# SCH_tic-tac_2024-06-27.net
KiCad netlist of a schematic drawn in EasyEDA
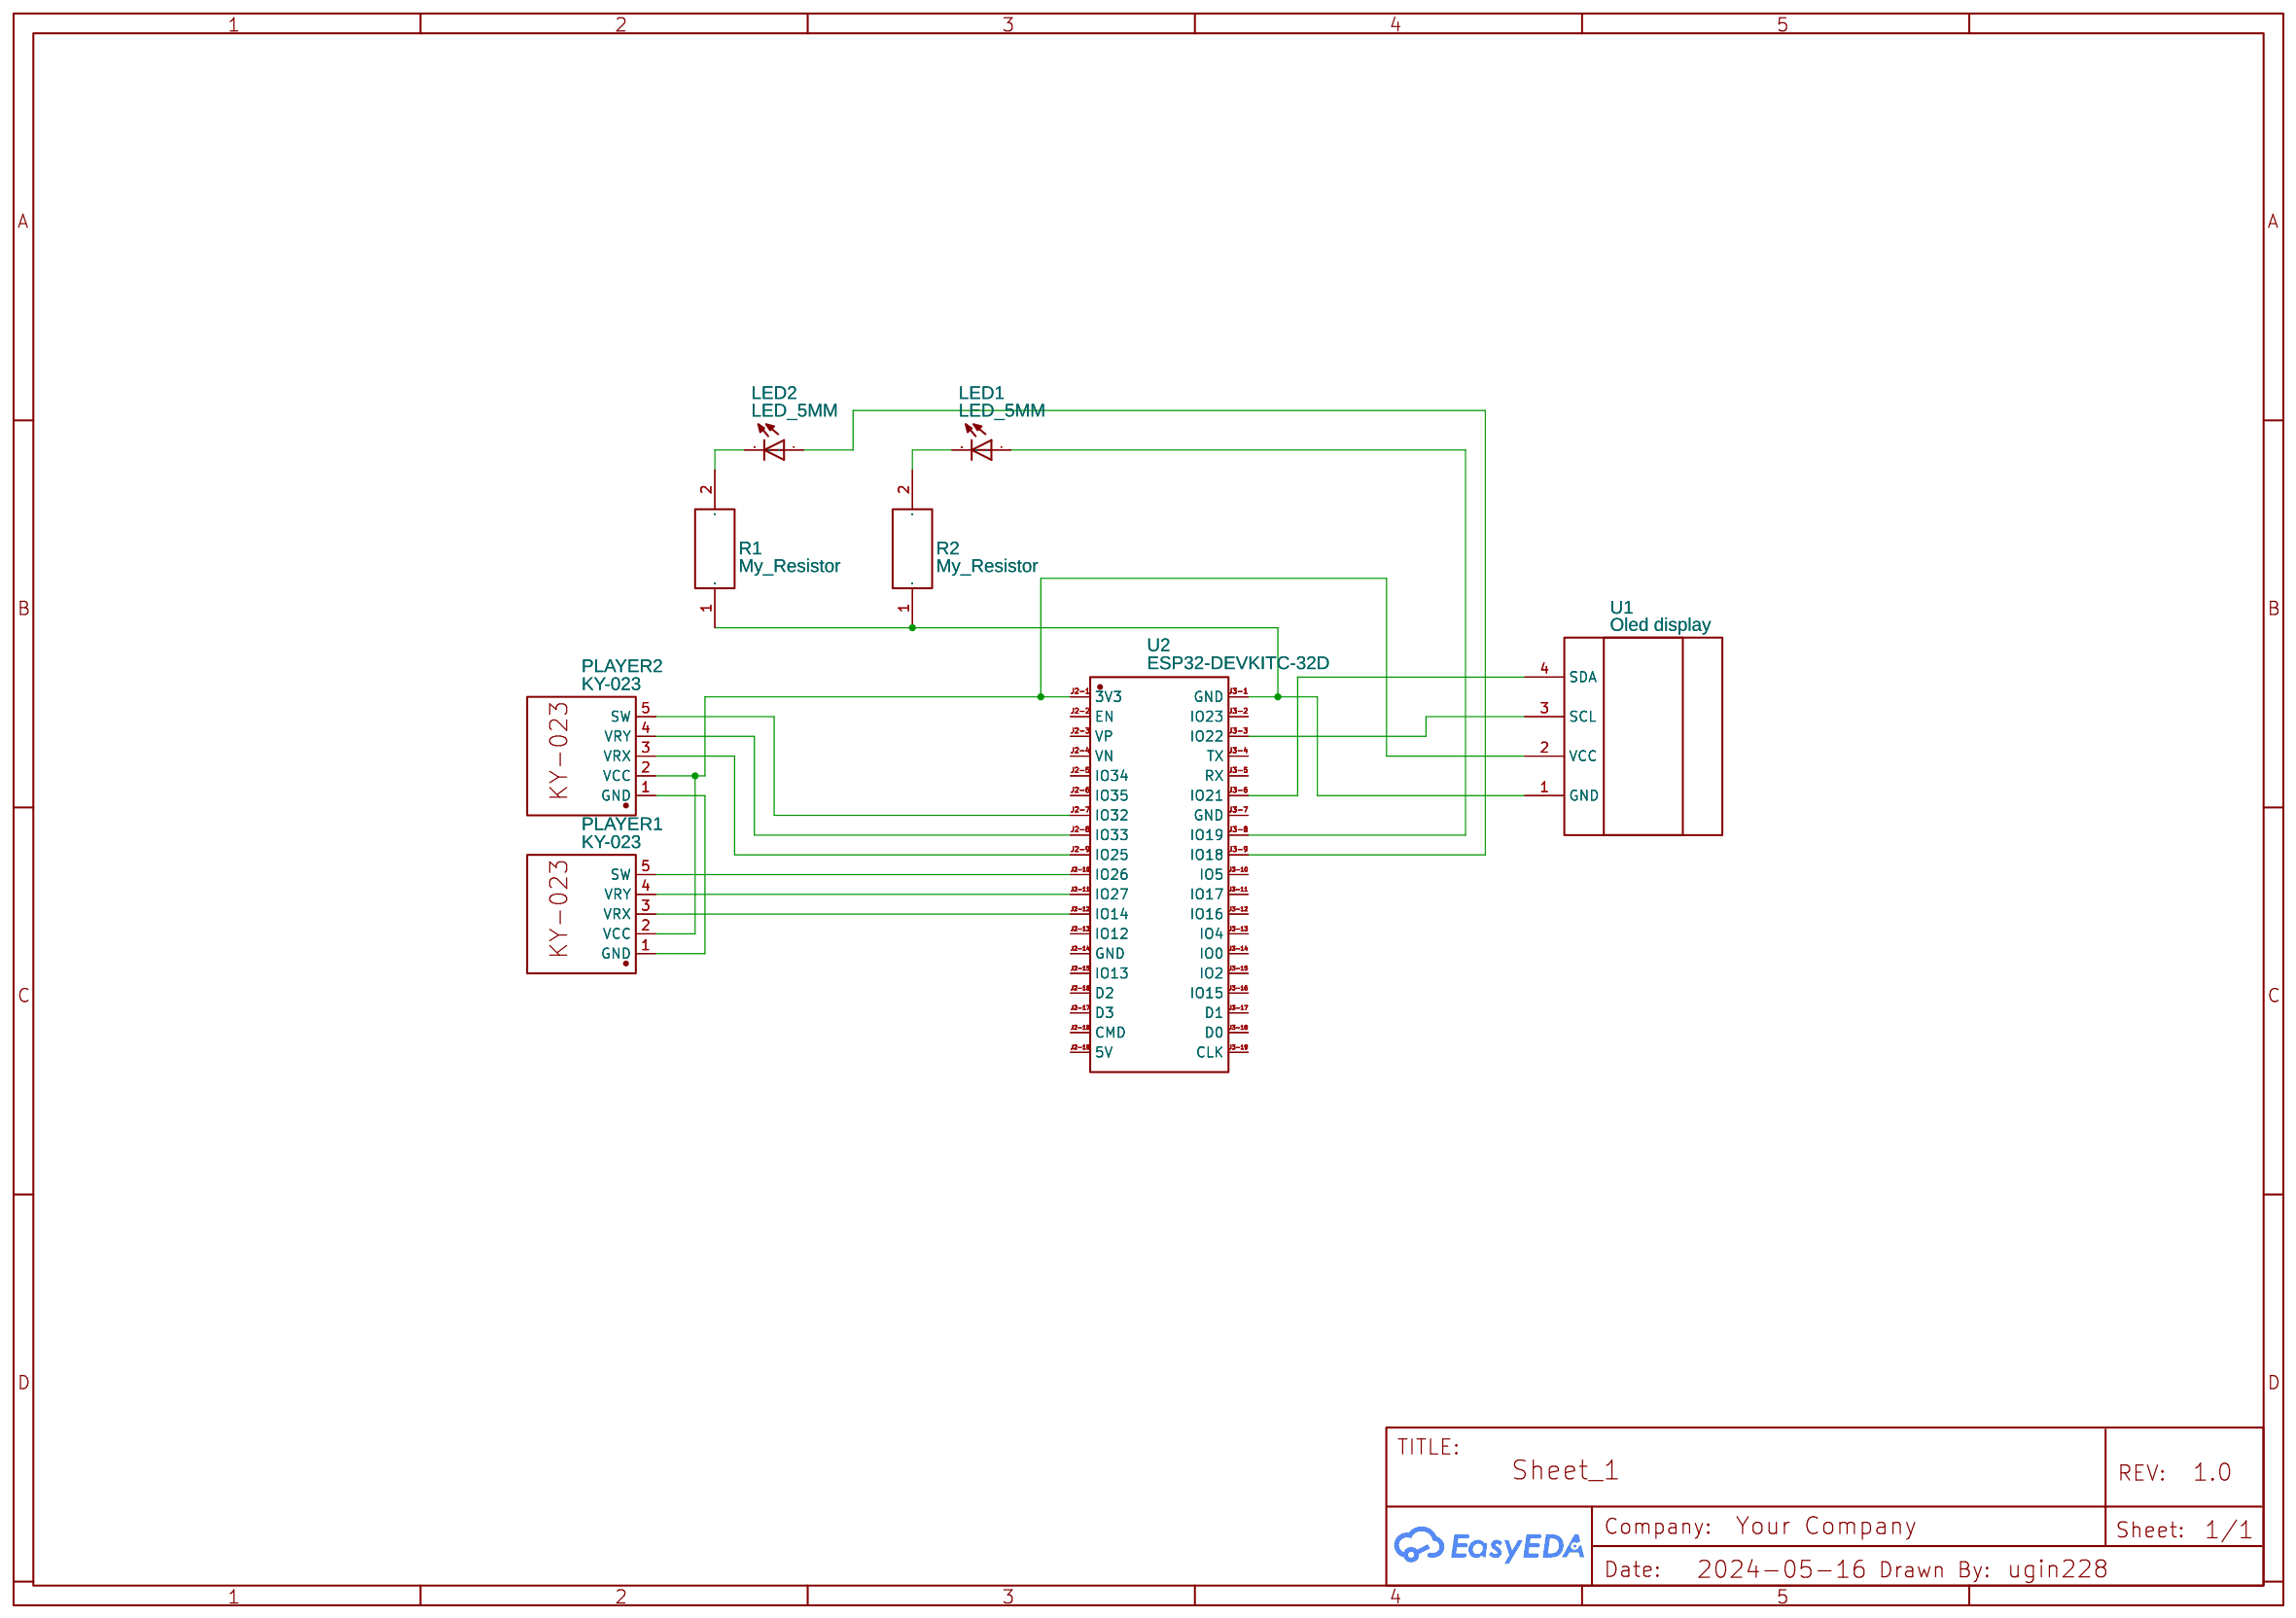
[diagram p0: schematic sheet]

(export (version "E")
  (design (tool "Eeschema 10.0.6"))
  (components
    (comp (ref "LED1") (value "LED_5MM") (libsource (lib "") (part "LED_5MM")))
    (comp (ref "LED2") (value "LED_5MM") (libsource (lib "") (part "LED_5MM")))
    (comp (ref "PLAYER1") (value "KY-023") (libsource (lib "") (part "KY-023")))
    (comp (ref "PLAYER2") (value "KY-023") (libsource (lib "") (part "KY-023")))
    (comp (ref "R1") (value "My_Resistor") (libsource (lib "") (part "My_Resistor")))
    (comp (ref "R2") (value "My_Resistor") (libsource (lib "") (part "My_Resistor")))
    (comp (ref "U1") (value "Oled display") (libsource (lib "") (part "Oled display")))
    (comp (ref "U2")
      (value "ESP32-DEVKITC-32D")
      (fields
        (field (name "Manufacturer Part") "ESP32-DevKitC-32D")
        (field (name "Manufacturer") "ESPRESSIF(乐鑫)")
      )
      (libsource (lib "") (part "ESP32-DEVKITC-32D"))
    )
  )
  (nets
    (net (code "1") (name "Net-(LED1-A)") (class "Default")
      (node (ref "LED1") (pin "1") (pinfunction "A_1") (pintype "unspecified"))
      (node (ref "U2") (pin "J3-8") (pinfunction "IO19_J3-8") (pintype "unspecified"))
    )
    (net (code "2") (name "Net-(LED1-C)") (class "Default")
      (node (ref "LED1") (pin "2") (pinfunction "C_2") (pintype "unspecified"))
      (node (ref "R2") (pin "2") (pinfunction "2_2") (pintype "unspecified"))
    )
    (net (code "3") (name "Net-(LED2-A)") (class "Default")
      (node (ref "LED2") (pin "1") (pinfunction "A_1") (pintype "unspecified"))
      (node (ref "U2") (pin "J3-9") (pinfunction "IO18_J3-9") (pintype "unspecified"))
    )
    (net (code "4") (name "Net-(LED2-C)") (class "Default")
      (node (ref "LED2") (pin "2") (pinfunction "C_2") (pintype "unspecified"))
      (node (ref "R1") (pin "2") (pinfunction "2_2") (pintype "unspecified"))
    )
    (net (code "5") (name "Net-(PLAYER1-GND)") (class "Default")
      (node (ref "PLAYER1") (pin "1") (pinfunction "GND_1") (pintype "unspecified"))
      (node (ref "PLAYER2") (pin "1") (pinfunction "GND_1") (pintype "unspecified"))
    )
    (net (code "6") (name "Net-(PLAYER1-SW)") (class "Default")
      (node (ref "PLAYER1") (pin "5") (pinfunction "SW_5") (pintype "unspecified"))
      (node (ref "U2") (pin "J2-10") (pinfunction "IO26_J2-10") (pintype "unspecified"))
    )
    (net (code "7") (name "Net-(PLAYER1-VCC)") (class "Default")
      (node (ref "PLAYER1") (pin "2") (pinfunction "VCC_2") (pintype "unspecified"))
      (node (ref "PLAYER2") (pin "2") (pinfunction "VCC_2") (pintype "unspecified"))
      (node (ref "U1") (pin "2") (pinfunction "VCC_2") (pintype "unspecified"))
      (node (ref "U2") (pin "J2-1") (pinfunction "3V3_J2-1") (pintype "unspecified"))
    )
    (net (code "8") (name "Net-(PLAYER1-VRX)") (class "Default")
      (node (ref "PLAYER1") (pin "3") (pinfunction "VRX_3") (pintype "unspecified"))
      (node (ref "U2") (pin "J2-12") (pinfunction "IO14_J2-12") (pintype "unspecified"))
    )
    (net (code "9") (name "Net-(PLAYER1-VRY)") (class "Default")
      (node (ref "PLAYER1") (pin "4") (pinfunction "VRY_4") (pintype "unspecified"))
      (node (ref "U2") (pin "J2-11") (pinfunction "IO27_J2-11") (pintype "unspecified"))
    )
    (net (code "10") (name "Net-(PLAYER2-SW)") (class "Default")
      (node (ref "PLAYER2") (pin "5") (pinfunction "SW_5") (pintype "unspecified"))
      (node (ref "U2") (pin "J2-7") (pinfunction "IO32_J2-7") (pintype "unspecified"))
    )
    (net (code "11") (name "Net-(PLAYER2-VRX)") (class "Default")
      (node (ref "PLAYER2") (pin "3") (pinfunction "VRX_3") (pintype "unspecified"))
      (node (ref "U2") (pin "J2-9") (pinfunction "IO25_J2-9") (pintype "unspecified"))
    )
    (net (code "12") (name "Net-(PLAYER2-VRY)") (class "Default")
      (node (ref "PLAYER2") (pin "4") (pinfunction "VRY_4") (pintype "unspecified"))
      (node (ref "U2") (pin "J2-8") (pinfunction "IO33_J2-8") (pintype "unspecified"))
    )
    (net (code "13") (name "Net-(U1-GND)") (class "Default")
      (node (ref "R1") (pin "1") (pinfunction "1_1") (pintype "unspecified"))
      (node (ref "R2") (pin "1") (pinfunction "1_1") (pintype "unspecified"))
      (node (ref "U1") (pin "1") (pinfunction "GND_1") (pintype "unspecified"))
      (node (ref "U2") (pin "J3-1") (pinfunction "GND_J3-1") (pintype "unspecified"))
    )
    (net (code "14") (name "Net-(U1-SCL)") (class "Default")
      (node (ref "U1") (pin "3") (pinfunction "SCL_3") (pintype "unspecified"))
      (node (ref "U2") (pin "J3-3") (pinfunction "IO22_J3-3") (pintype "unspecified"))
    )
    (net (code "15") (name "Net-(U1-SDA)") (class "Default")
      (node (ref "U1") (pin "4") (pinfunction "SDA_4") (pintype "unspecified"))
      (node (ref "U2") (pin "J3-6") (pinfunction "IO21_J3-6") (pintype "unspecified"))
    )
    (net (code "16") (name "unconnected-(U2-5V-PadJ2-19)") (class "Default")
      (node (ref "U2") (pin "J2-19") (pinfunction "5V_J2-19") (pintype "unspecified"))
    )
    (net (code "17") (name "unconnected-(U2-CLK-PadJ3-19)") (class "Default")
      (node (ref "U2") (pin "J3-19") (pinfunction "CLK_J3-19") (pintype "unspecified"))
    )
    (net (code "18") (name "unconnected-(U2-CMD-PadJ2-18)") (class "Default")
      (node (ref "U2") (pin "J2-18") (pinfunction "CMD_J2-18") (pintype "unspecified"))
    )
    (net (code "19") (name "unconnected-(U2-D0-PadJ3-18)") (class "Default")
      (node (ref "U2") (pin "J3-18") (pinfunction "D0_J3-18") (pintype "unspecified"))
    )
    (net (code "20") (name "unconnected-(U2-D1-PadJ3-17)") (class "Default")
      (node (ref "U2") (pin "J3-17") (pinfunction "D1_J3-17") (pintype "unspecified"))
    )
    (net (code "21") (name "unconnected-(U2-D2-PadJ2-16)") (class "Default")
      (node (ref "U2") (pin "J2-16") (pinfunction "D2_J2-16") (pintype "unspecified"))
    )
    (net (code "22") (name "unconnected-(U2-D3-PadJ2-17)") (class "Default")
      (node (ref "U2") (pin "J2-17") (pinfunction "D3_J2-17") (pintype "unspecified"))
    )
    (net (code "23") (name "unconnected-(U2-EN-PadJ2-2)") (class "Default")
      (node (ref "U2") (pin "J2-2") (pinfunction "EN_J2-2") (pintype "unspecified"))
    )
    (net (code "24") (name "unconnected-(U2-GND-PadJ2-14)") (class "Default")
      (node (ref "U2") (pin "J2-14") (pinfunction "GND_J2-14") (pintype "unspecified"))
    )
    (net (code "25") (name "unconnected-(U2-GND-PadJ3-7)") (class "Default")
      (node (ref "U2") (pin "J3-7") (pinfunction "GND_J3-7") (pintype "unspecified"))
    )
    (net (code "26") (name "unconnected-(U2-IO0-PadJ3-14)") (class "Default")
      (node (ref "U2") (pin "J3-14") (pinfunction "IO0_J3-14") (pintype "unspecified"))
    )
    (net (code "27") (name "unconnected-(U2-IO2-PadJ3-15)") (class "Default")
      (node (ref "U2") (pin "J3-15") (pinfunction "IO2_J3-15") (pintype "unspecified"))
    )
    (net (code "28") (name "unconnected-(U2-IO4-PadJ3-13)") (class "Default")
      (node (ref "U2") (pin "J3-13") (pinfunction "IO4_J3-13") (pintype "unspecified"))
    )
    (net (code "29") (name "unconnected-(U2-IO5-PadJ3-10)") (class "Default")
      (node (ref "U2") (pin "J3-10") (pinfunction "IO5_J3-10") (pintype "unspecified"))
    )
    (net (code "30") (name "unconnected-(U2-IO12-PadJ2-13)") (class "Default")
      (node (ref "U2") (pin "J2-13") (pinfunction "IO12_J2-13") (pintype "unspecified"))
    )
    (net (code "31") (name "unconnected-(U2-IO13-PadJ2-15)") (class "Default")
      (node (ref "U2") (pin "J2-15") (pinfunction "IO13_J2-15") (pintype "unspecified"))
    )
    (net (code "32") (name "unconnected-(U2-IO15-PadJ3-16)") (class "Default")
      (node (ref "U2") (pin "J3-16") (pinfunction "IO15_J3-16") (pintype "unspecified"))
    )
    (net (code "33") (name "unconnected-(U2-IO16-PadJ3-12)") (class "Default")
      (node (ref "U2") (pin "J3-12") (pinfunction "IO16_J3-12") (pintype "unspecified"))
    )
    (net (code "34") (name "unconnected-(U2-IO17-PadJ3-11)") (class "Default")
      (node (ref "U2") (pin "J3-11") (pinfunction "IO17_J3-11") (pintype "unspecified"))
    )
    (net (code "35") (name "unconnected-(U2-IO23-PadJ3-2)") (class "Default")
      (node (ref "U2") (pin "J3-2") (pinfunction "IO23_J3-2") (pintype "unspecified"))
    )
    (net (code "36") (name "unconnected-(U2-IO34-PadJ2-5)") (class "Default")
      (node (ref "U2") (pin "J2-5") (pinfunction "IO34_J2-5") (pintype "unspecified"))
    )
    (net (code "37") (name "unconnected-(U2-IO35-PadJ2-6)") (class "Default")
      (node (ref "U2") (pin "J2-6") (pinfunction "IO35_J2-6") (pintype "unspecified"))
    )
    (net (code "38") (name "unconnected-(U2-RX-PadJ3-5)") (class "Default")
      (node (ref "U2") (pin "J3-5") (pinfunction "RX_J3-5") (pintype "unspecified"))
    )
    (net (code "39") (name "unconnected-(U2-TX-PadJ3-4)") (class "Default")
      (node (ref "U2") (pin "J3-4") (pinfunction "TX_J3-4") (pintype "unspecified"))
    )
    (net (code "40") (name "unconnected-(U2-VN-PadJ2-4)") (class "Default")
      (node (ref "U2") (pin "J2-4") (pinfunction "VN_J2-4") (pintype "unspecified"))
    )
    (net (code "41") (name "unconnected-(U2-VP-PadJ2-3)") (class "Default")
      (node (ref "U2") (pin "J2-3") (pinfunction "VP_J2-3") (pintype "unspecified"))
    )
  )
)
